# filter-4.net
KiCad netlist of a schematic drawn in Altium Designer
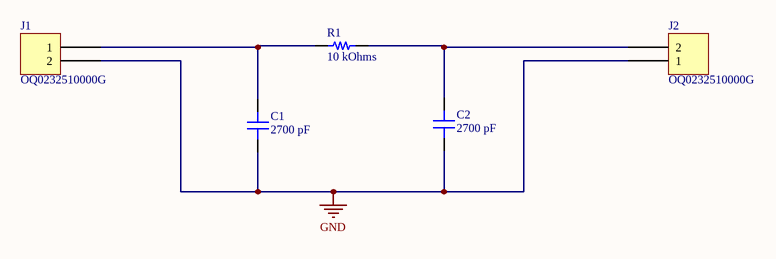
[diagram p0: filter-4.SchDoc]

(export (version "E")
  (design (tool "Eeschema 10.0.6"))
  (components
    (comp (ref "C1")
      (value "2700 pF")
      (footprint "CAP 0603_1608")
      (description "CAP CER 2700PF 25V NP0 0603")
      (fields (field (name "PART NUMBER") "C0603C272F3GAC7867") (field (name "MANUFACTURER") "KEMET"))
      (libsource (lib "Celestial Altium Library - altium_library") (part "Capacitor"))
    )
    (comp (ref "C2")
      (value "2700 pF")
      (footprint "CAP 0603_1608")
      (description "CAP CER 2700PF 25V NP0 0603")
      (fields (field (name "PART NUMBER") "C0603C272F3GAC7867") (field (name "MANUFACTURER") "KEMET"))
      (libsource (lib "Celestial Altium Library - altium_library") (part "Capacitor"))
    )
    (comp (ref "J1")
      (value "OQ0232510000G")
      (footprint "FCI 06-381-2PIN")
      (description "TERM BLOCK HDR 2POS 90DEG 3.81MM")
      (fields (field (name "MANUFACTURER") "Amphenol Anytek"))
      (libsource (lib "") (part "2 Pin_1"))
    )
    (comp (ref "J2")
      (value "OQ0232510000G")
      (footprint "FCI 06-381-2PIN")
      (description "TERM BLOCK HDR 2POS 90DEG 3.81MM")
      (fields (field (name "MANUFACTURER") "Amphenol Anytek"))
      (libsource (lib "Celestial Altium Library - altium_library") (part "2 Pin"))
    )
    (comp (ref "R1")
      (value "10 kOhms")
      (footprint "RES 0603_1608")
      (description "RES 10K OHM 0.1% 1/16W 0603")
      (fields
        (field (name "PART NUMBER") "RNCS0603BKE10K0")
        (field (name "MANUFACTURER") "Stackpole Electronics Inc")
      )
      (libsource (lib "Celestial Altium Library - altium_library") (part "Resistor"))
    )
  )
  (nets
    (net (code "1") (name "GND") (class "Default")
      (node (ref "C1") (pin "1") (pinfunction "1_1") (pintype "passive"))
      (node (ref "C2") (pin "1") (pinfunction "1_1") (pintype "passive"))
      (node (ref "J1") (pin "2") (pinfunction "2_2") (pintype "passive"))
      (node (ref "J2") (pin "1") (pinfunction "1_1") (pintype "passive"))
    )
    (net (code "2") (name "Net-(C1-Pad2)") (class "Default")
      (node (ref "C1") (pin "2") (pinfunction "2_2") (pintype "passive"))
      (node (ref "J1") (pin "1") (pinfunction "1_1") (pintype "passive"))
      (node (ref "R1") (pin "1") (pinfunction "1_1") (pintype "passive"))
    )
    (net (code "3") (name "Net-(C2-Pad2)") (class "Default")
      (node (ref "C2") (pin "2") (pinfunction "2_2") (pintype "passive"))
      (node (ref "J2") (pin "2") (pinfunction "2_2") (pintype "passive"))
      (node (ref "R1") (pin "2") (pinfunction "2_2") (pintype "passive"))
    )
  )
)
